# FMC_ADC_top.net
KiCad netlist of a schematic drawn in Altium Designer
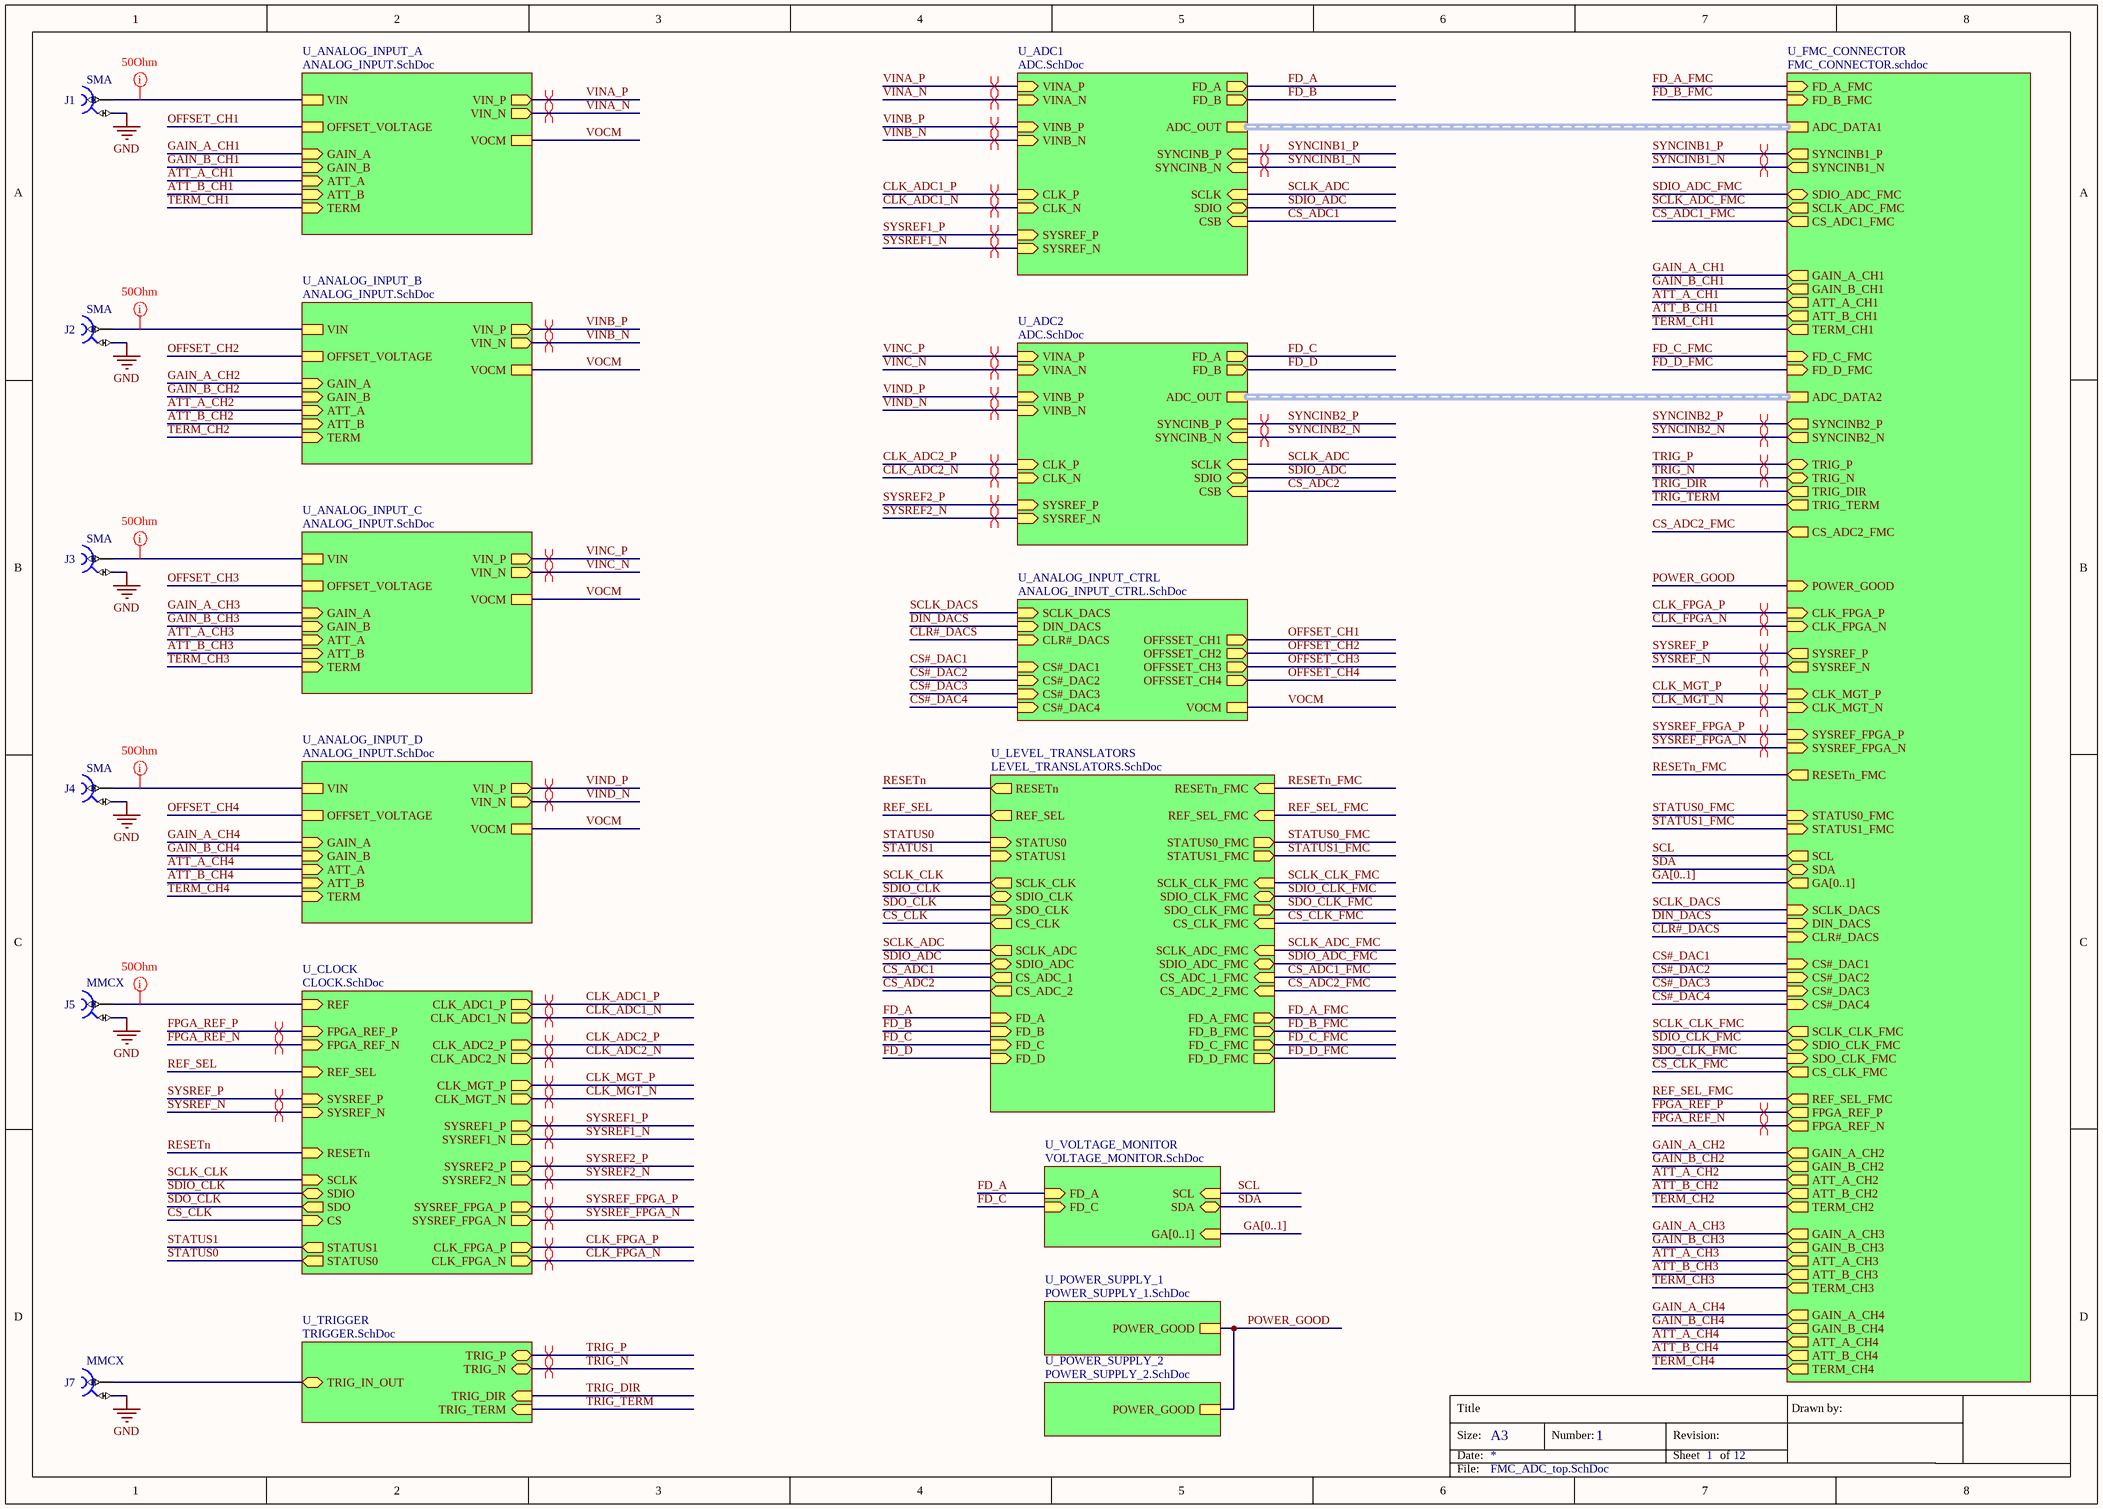
[diagram p0: FMC_ADC_top.SchDoc]

(export (version "E")
  (design (tool "Eeschema 10.0.6"))
  (components
    (comp (ref "J1")
      (value "SMA")
      (footprint "HUBER-SUHNER_85_SMA-50-0-101/111_NE")
      (fields
        (field (name "PART NUMBER") "HUBER-SUHNER_85_SMA-50-0-101/111_NE")
        (field (name "MANUFACTURER") "HUBER+SUHNER")
        (field (name "MANUFACTURER PART NUMBER") "85_SMA-50-0-101/111_NE")
        (field (name "AUTHOR") "CERN DEM JLC")
      )
      (libsource (lib "Connectors") (part "Coax_1Female_1Shield"))
    )
    (comp (ref "J2")
      (value "SMA")
      (footprint "HUBER-SUHNER_85_SMA-50-0-101/111_NE")
      (fields
        (field (name "PART NUMBER") "HUBER-SUHNER_85_SMA-50-0-101/111_NE")
        (field (name "MANUFACTURER") "HUBER+SUHNER")
        (field (name "MANUFACTURER PART NUMBER") "85_SMA-50-0-101/111_NE")
        (field (name "AUTHOR") "CERN DEM JLC")
      )
      (libsource (lib "Connectors") (part "Coax_1Female_1Shield"))
    )
    (comp (ref "J3")
      (value "SMA")
      (footprint "HUBER-SUHNER_85_SMA-50-0-101/111_NE")
      (fields
        (field (name "PART NUMBER") "HUBER-SUHNER_85_SMA-50-0-101/111_NE")
        (field (name "MANUFACTURER") "HUBER+SUHNER")
        (field (name "MANUFACTURER PART NUMBER") "85_SMA-50-0-101/111_NE")
        (field (name "AUTHOR") "CERN DEM JLC")
      )
      (libsource (lib "Connectors") (part "Coax_1Female_1Shield"))
    )
    (comp (ref "J4")
      (value "SMA")
      (footprint "HUBER-SUHNER_85_SMA-50-0-101/111_NE")
      (fields
        (field (name "PART NUMBER") "HUBER-SUHNER_85_SMA-50-0-101/111_NE")
        (field (name "MANUFACTURER") "HUBER+SUHNER")
        (field (name "MANUFACTURER PART NUMBER") "85_SMA-50-0-101/111_NE")
        (field (name "AUTHOR") "CERN DEM JLC")
      )
      (libsource (lib "Connectors") (part "Coax_1Female_1Shield"))
    )
    (comp (ref "J5")
      (value "Coax_1Female_1Shield")
      (footprint "HUBER-SUHNER_85_MMCX-50-0-1/111_OE")
      (fields
        (field (name "PART NUMBER") "HUBER-SUHNER_85_MMCX-50-0-1/111_OE")
        (field (name "FAMILY") "MMCX")
        (field (name "MANUFACTURER") "HUBER+SUHNER")
        (field (name "MANUFACTURER PART NUMBER") "85_MMCX-50-0-1/111_OE")
        (field (name "AUTHOR") "CERN DEM JLC")
      )
      (libsource (lib "Connectors") (part "Coax_1Female_1Shield"))
    )
    (comp (ref "J7")
      (value "Coax_1Female_1Shield")
      (footprint "HUBER-SUHNER_85_MMCX-50-0-1/111_OE")
      (fields
        (field (name "PART NUMBER") "HUBER-SUHNER_85_MMCX-50-0-1/111_OE")
        (field (name "FAMILY") "MMCX")
        (field (name "MANUFACTURER") "HUBER+SUHNER")
        (field (name "MANUFACTURER PART NUMBER") "85_MMCX-50-0-1/111_OE")
        (field (name "AUTHOR") "CERN DEM JLC")
      )
      (libsource (lib "Connectors") (part "Coax_1Female_1Shield"))
    )
  )
  (nets
    (net (code "57") (name "/REF") (class "Default")
      (node (ref "J5") (pin "1") (pinfunction "1_1") (pintype "bidirectional"))
    )
    (net (code "96") (name "/TRIG_IN_OUT") (class "Default")
      (node (ref "J7") (pin "1") (pinfunction "1_1") (pintype "bidirectional"))
    )
    (net (code "100") (name "/VIN") (class "Default")
      (node (ref "J3") (pin "1") (pinfunction "1_1") (pintype "bidirectional"))
    )
    (net (code "109") (name "/VIN_1") (class "Default")
      (node (ref "J1") (pin "1") (pinfunction "1_1") (pintype "bidirectional"))
    )
    (net (code "110") (name "/VIN_2") (class "Default")
      (node (ref "J2") (pin "1") (pinfunction "1_1") (pintype "bidirectional"))
    )
    (net (code "111") (name "/VIN_3") (class "Default")
      (node (ref "J4") (pin "1") (pinfunction "1_1") (pintype "bidirectional"))
    )
    (net (code "113") (name "GND") (class "Default")
      (node (ref "J1") (pin "2") (pinfunction "2_2") (pintype "bidirectional"))
      (node (ref "J2") (pin "2") (pinfunction "2_2") (pintype "bidirectional"))
      (node (ref "J3") (pin "2") (pinfunction "2_2") (pintype "bidirectional"))
      (node (ref "J4") (pin "2") (pinfunction "2_2") (pintype "bidirectional"))
      (node (ref "J5") (pin "2") (pinfunction "2_2") (pintype "bidirectional"))
      (node (ref "J7") (pin "2") (pinfunction "2_2") (pintype "bidirectional"))
    )
  )
)
